# HIVDC_v1p1.net
KiCad netlist of a schematic drawn in EAGLE
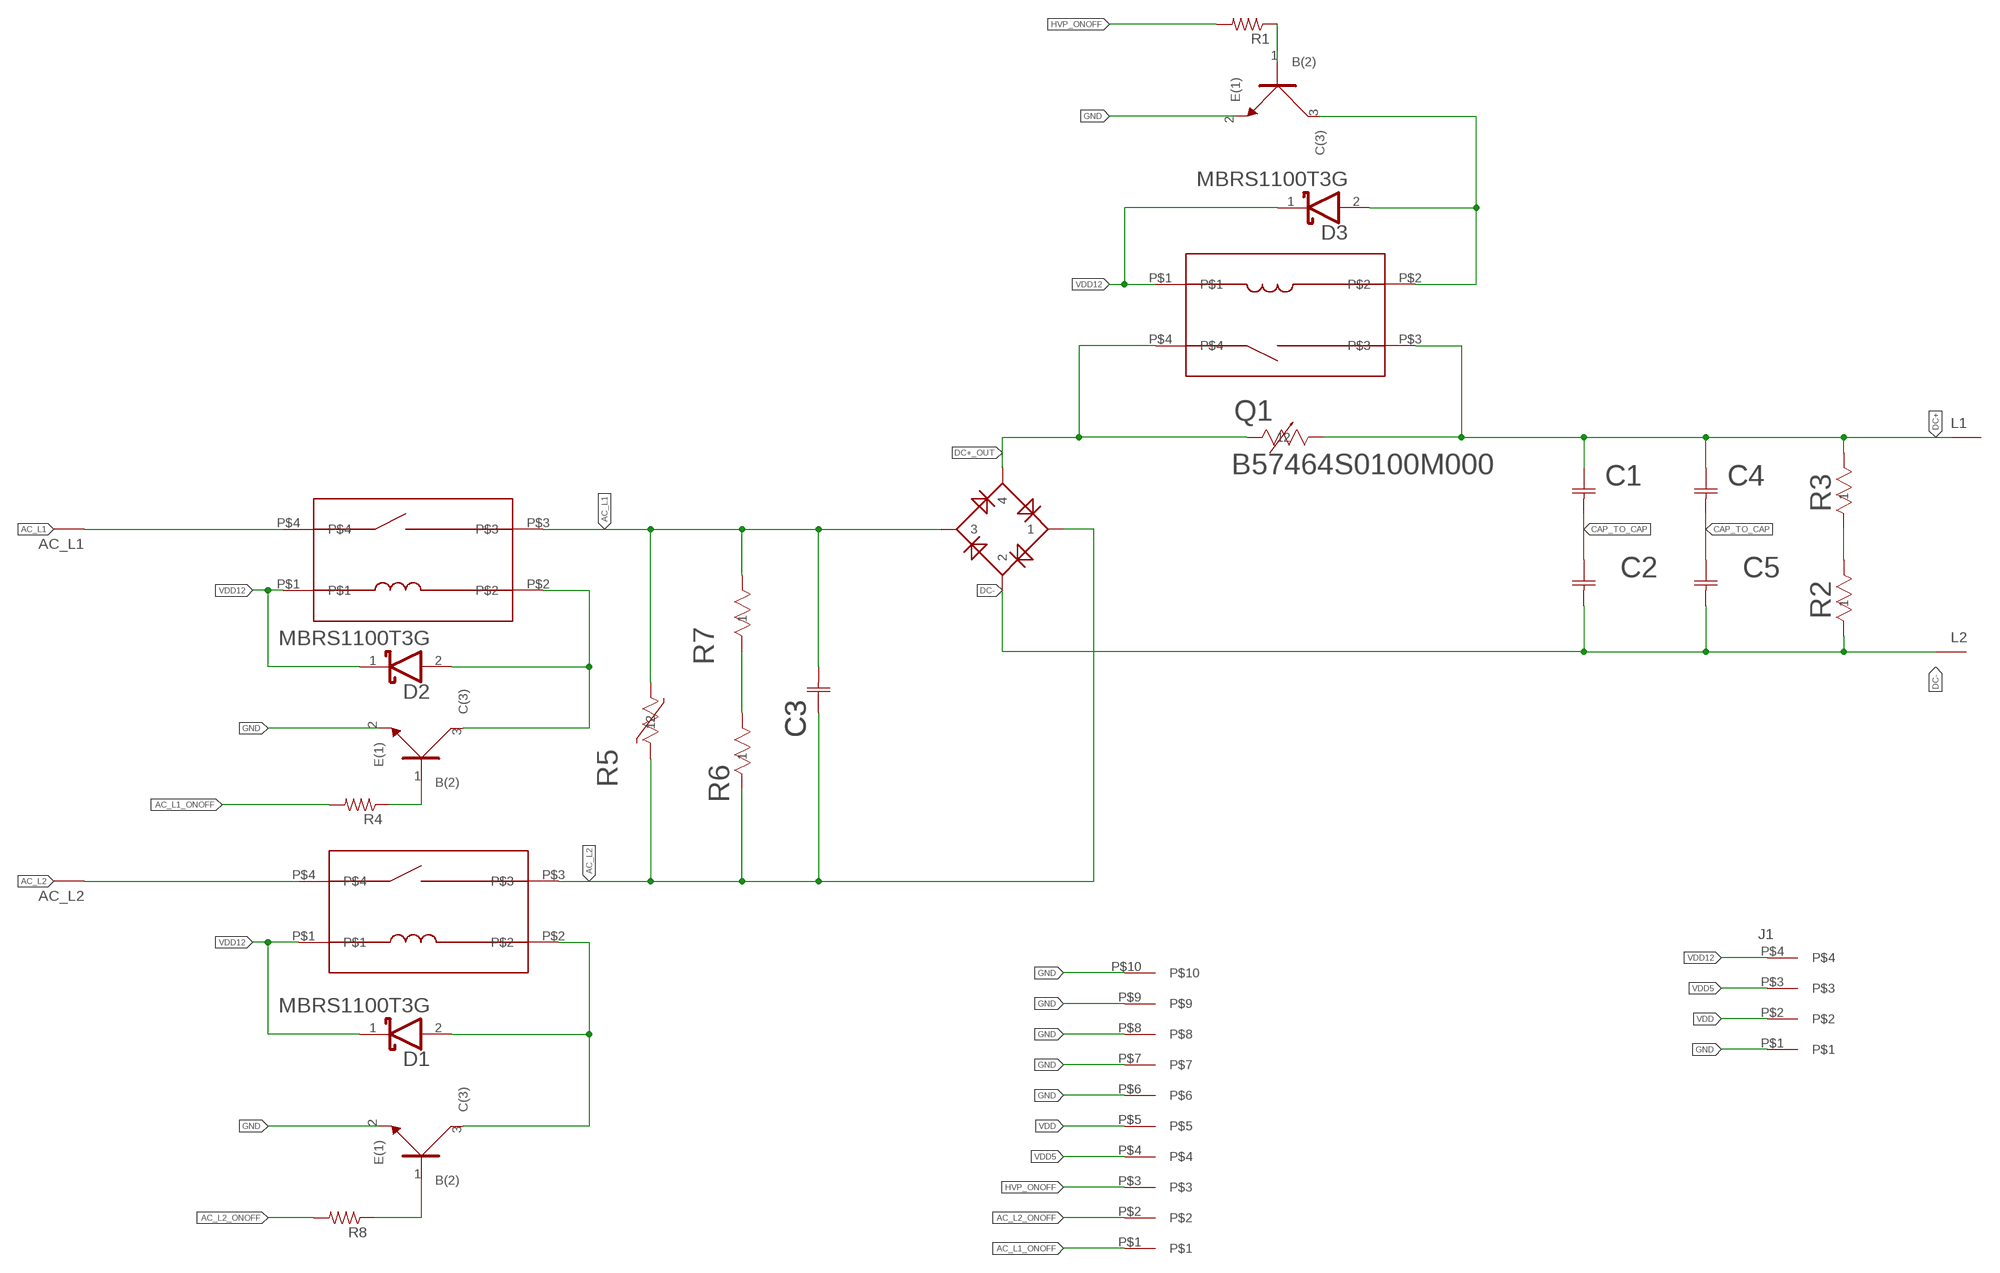
[diagram p0: schematic, sheet 1]

(export (version "E")
  (design (tool "Eeschema 10.0.6"))
  (components
    (comp (ref "AC_L1")
      (value "AC_240V_N_15A")
      (footprint "eagle-import:AC_240V_L1_15A")
      (libsource (lib "eagle-import") (part "AC_240V_N_15A"))
    )
    (comp (ref "AC_L2")
      (value "AC_240V_L_15A")
      (footprint "eagle-import:AC_240V_L1_15A")
      (libsource (lib "eagle-import") (part "AC_240V_L_15A"))
    )
    (comp (ref "C1")
      (value "SLP152M250H9P3")
      (footprint "eagle-import:CAP_SLP152M250H9P3_CND")
      (fields (field (name "COPYRIGHT") "Copyright (C) 2018 Accelerated Designs. All rights reserved"))
      (libsource (lib "eagle-import") (part "SLP152M250H9P3"))
    )
    (comp (ref "C2")
      (value "SLP152M250H9P3")
      (footprint "eagle-import:CAP_SLP152M250H9P3_CND")
      (fields (field (name "COPYRIGHT") "Copyright (C) 2018 Accelerated Designs. All rights reserved"))
      (libsource (lib "eagle-import") (part "SLP152M250H9P3"))
    )
    (comp (ref "C3")
      (value "B32922C3104K")
      (footprint "eagle-import:CAP_5.0_X_10.5_X_18.0_EPC")
      (libsource (lib "eagle-import") (part "B32922C3104K"))
    )
    (comp (ref "C4")
      (value "SLP152M250H9P3")
      (footprint "eagle-import:CAP_SLP152M250H9P3_CND")
      (fields (field (name "COPYRIGHT") "Copyright (C) 2018 Accelerated Designs. All rights reserved"))
      (libsource (lib "eagle-import") (part "SLP152M250H9P3"))
    )
    (comp (ref "C5")
      (value "SLP152M250H9P3")
      (footprint "eagle-import:CAP_SLP152M250H9P3_CND")
      (fields (field (name "COPYRIGHT") "Copyright (C) 2018 Accelerated Designs. All rights reserved"))
      (libsource (lib "eagle-import") (part "SLP152M250H9P3"))
    )
    (comp (ref "D1")
      (value "MBRS1100T3GON_SEMI_MBRS1100T3G_0_0")
      (footprint "eagle-import:SMB")
      (fields
        (field (name "3DS_PART_NUMBER") "417-00000")
        (field (name "DIGIKEY_PART_NUMBER") "MBRS1100T3GOSCT-ND")
        (field (name "MF") "ON Semi")
      )
      (libsource (lib "eagle-import") (part "MBRS1100T3GON_SEMI_MBRS1100T3G_0_0"))
    )
    (comp (ref "D2")
      (value "MBRS1100T3GON_SEMI_MBRS1100T3G_0_0")
      (footprint "eagle-import:SMB")
      (fields
        (field (name "3DS_PART_NUMBER") "417-00000")
        (field (name "DIGIKEY_PART_NUMBER") "MBRS1100T3GOSCT-ND")
        (field (name "MF") "ON Semi")
      )
      (libsource (lib "eagle-import") (part "MBRS1100T3GON_SEMI_MBRS1100T3G_0_0"))
    )
    (comp (ref "D3")
      (value "MBRS1100T3GON_SEMI_MBRS1100T3G_0_0")
      (footprint "eagle-import:SMB")
      (fields
        (field (name "3DS_PART_NUMBER") "417-00000")
        (field (name "DIGIKEY_PART_NUMBER") "MBRS1100T3GOSCT-ND")
        (field (name "MF") "ON Semi")
      )
      (libsource (lib "eagle-import") (part "MBRS1100T3GON_SEMI_MBRS1100T3G_0_0"))
    )
    (comp (ref "J1")
      (value "4-pos")
      (footprint "eagle-import:1X4_3.81MM_PITCH")
      (fields (field (name "PARTNO") "691322310004"))
      (libsource (lib "eagle-import") (part "3.81MM_1_X_4_RT_ANGLE_PLUG_HEADER"))
    )
    (comp (ref "L1")
      (value "DC_HI_V")
      (footprint "eagle-import:AC_240V_L1_15A")
      (libsource (lib "eagle-import") (part "DC_HI_V"))
    )
    (comp (ref "L2")
      (value "DC_HI_V")
      (footprint "eagle-import:AC_240V_L1_15A")
      (libsource (lib "eagle-import") (part "DC_HI_V"))
    )
    (comp (ref "Q1")
      (value "B57464S0100M000")
      (footprint "eagle-import:TRES_B57464S0XXXM000_EPC")
      (fields (field (name "COPYRIGHT") "Copyright (C) 2018 Accelerated Designs. All rights reserved"))
      (libsource (lib "eagle-import") (part "B57464S0100M000"))
    )
    (comp (ref "R1")
      (value "R_0402")
      (footprint "eagle-import:0402")
      (libsource (lib "eagle-import") (part "R_0402"))
    )
    (comp (ref "R2")
      (value "CRCW1206220KJNEAHPRES_V1206_VIS-M")
      (footprint "eagle-import:RES_V1206_VIS-M")
      (fields (field (name "MANUFACTURER_PART_NUMBER") "CRCW1206220KJNEAHP"))
      (libsource (lib "eagle-import") (part "CRCW1206220KJNEAHPRES_V1206_VIS-M"))
    )
    (comp (ref "R3")
      (value "CRCW1206220KJNEAHPRES_V1206_VIS-M")
      (footprint "eagle-import:RES_V1206_VIS-M")
      (fields (field (name "MANUFACTURER_PART_NUMBER") "CRCW1206220KJNEAHP"))
      (libsource (lib "eagle-import") (part "CRCW1206220KJNEAHPRES_V1206_VIS-M"))
    )
    (comp (ref "R4")
      (value "R_0402")
      (footprint "eagle-import:0402")
      (libsource (lib "eagle-import") (part "R_0402"))
    )
    (comp (ref "R5")
      (value "VDRUS10T510BSE")
      (footprint "eagle-import:VRES_VDRUS10T460BSE_VIS")
      (fields (field (name "COPYRIGHT") "Copyright (C) 2018 Accelerated Designs. All rights reserved"))
      (libsource (lib "eagle-import") (part "VDRUS10T510BSE"))
    )
    (comp (ref "R6")
      (value "CRCW1206220KJNEAHPRES_V1206_VIS-M")
      (footprint "eagle-import:RES_V1206_VIS-M")
      (fields (field (name "MANUFACTURER_PART_NUMBER") "CRCW1206220KJNEAHP"))
      (libsource (lib "eagle-import") (part "CRCW1206220KJNEAHPRES_V1206_VIS-M"))
    )
    (comp (ref "R7")
      (value "CRCW1206220KJNEAHPRES_V1206_VIS-M")
      (footprint "eagle-import:RES_V1206_VIS-M")
      (fields (field (name "MANUFACTURER_PART_NUMBER") "CRCW1206220KJNEAHP"))
      (libsource (lib "eagle-import") (part "CRCW1206220KJNEAHPRES_V1206_VIS-M"))
    )
    (comp (ref "R8")
      (value "R_0402")
      (footprint "eagle-import:0402")
      (libsource (lib "eagle-import") (part "R_0402"))
    )
    (comp (ref "RL1")
      (value "J120D1AS12VDCP")
      (footprint "eagle-import:J120D")
      (libsource (lib "eagle-import") (part "J120D1AS12VDCP"))
    )
    (comp (ref "RL2")
      (value "J120D1AS12VDCP")
      (footprint "eagle-import:J120D")
      (libsource (lib "eagle-import") (part "J120D1AS12VDCP"))
    )
    (comp (ref "RL3")
      (value "J120D1AS12VDCP")
      (footprint "eagle-import:J120D")
      (libsource (lib "eagle-import") (part "J120D1AS12VDCP"))
    )
    (comp (ref "U$1")
      (value "KBPC5010W-G")
      (footprint "eagle-import:KBPC-W_THRU")
      (libsource (lib "eagle-import") (part "KBPC5010W-G"))
    )
    (comp (ref "U$3")
      (value "1_X_10_HEADER_GENERIC_.1INCH")
      (footprint "eagle-import:HEADER_1_X_10_.1_INCH")
      (libsource (lib "eagle-import") (part "1_X_10_HEADER_GENERIC_.1INCH"))
    )
    (comp (ref "U1")
      (value "NPN")
      (footprint "eagle-import:SOT323")
      (fields (field (name "PARTNO") "BC846BW_NPN"))
      (libsource (lib "eagle-import") (part "BC846BW"))
    )
    (comp (ref "U2")
      (value "NPN")
      (footprint "eagle-import:SOT323")
      (fields (field (name "PARTNO") "BC846BW_NPN"))
      (libsource (lib "eagle-import") (part "BC846BW"))
    )
    (comp (ref "U3")
      (value "NPN")
      (footprint "eagle-import:SOT323")
      (fields (field (name "PARTNO") "BC846BW_NPN"))
      (libsource (lib "eagle-import") (part "BC846BW"))
    )
  )
  (nets
    (net (code "1") (name "AC_L1") (class "Default")
      (node (ref "AC_L1") (pin "P$1") (pinfunction "P$1_P$1") (pintype "passive"))
      (node (ref "C3") (pin "2") (pinfunction "2_2") (pintype "passive"))
      (node (ref "R5") (pin "1") (pinfunction "11_1") (pintype "passive"))
      (node (ref "R7") (pin "2") (pinfunction "2_2") (pintype "passive"))
      (node (ref "RL2") (pin "P$3") (pinfunction "P$3_P$3") (pintype "bidirectional"))
      (node (ref "RL2") (pin "P$4") (pinfunction "P$4_P$4") (pintype "bidirectional"))
      (node (ref "U$1") (pin "3") (pinfunction "3_3") (pintype "passive"))
    )
    (net (code "2") (name "AC_L1_ONOFF") (class "Default")
      (node (ref "R4") (pin "P$2") (pinfunction "2_P$2") (pintype "passive"))
      (node (ref "U$3") (pin "P$1") (pinfunction "P$1_P$1") (pintype "bidirectional"))
    )
    (net (code "3") (name "AC_L2") (class "Default")
      (node (ref "AC_L2") (pin "P$1") (pinfunction "P$1_P$1") (pintype "passive"))
      (node (ref "C3") (pin "1") (pinfunction "1_1") (pintype "passive"))
      (node (ref "R5") (pin "2") (pinfunction "12_2") (pintype "passive"))
      (node (ref "R6") (pin "1") (pinfunction "1_1") (pintype "passive"))
      (node (ref "RL3") (pin "P$3") (pinfunction "P$3_P$3") (pintype "bidirectional"))
      (node (ref "RL3") (pin "P$4") (pinfunction "P$4_P$4") (pintype "bidirectional"))
      (node (ref "U$1") (pin "1") (pinfunction "1_1") (pintype "passive"))
    )
    (net (code "4") (name "AC_L2_ONOFF") (class "Default")
      (node (ref "R8") (pin "P$2") (pinfunction "2_P$2") (pintype "passive"))
      (node (ref "U$3") (pin "P$2") (pinfunction "P$2_P$2") (pintype "bidirectional"))
    )
    (net (code "5") (name "CAP_TO_CAP") (class "Default")
      (node (ref "C1") (pin "2") (pinfunction "2_2") (pintype "passive"))
      (node (ref "C2") (pin "1") (pinfunction "1_1") (pintype "passive"))
      (node (ref "C4") (pin "2") (pinfunction "2_2") (pintype "passive"))
      (node (ref "C5") (pin "1") (pinfunction "1_1") (pintype "passive"))
    )
    (net (code "6") (name "DC+") (class "Default")
      (node (ref "C1") (pin "1") (pinfunction "1_1") (pintype "passive"))
      (node (ref "C4") (pin "1") (pinfunction "1_1") (pintype "passive"))
      (node (ref "L1") (pin "P$1") (pinfunction "P$1_P$1") (pintype "passive"))
      (node (ref "Q1") (pin "1") (pinfunction "11_1") (pintype "passive"))
      (node (ref "R3") (pin "2") (pinfunction "2_2") (pintype "passive"))
      (node (ref "RL1") (pin "P$3") (pinfunction "P$3_P$3") (pintype "bidirectional"))
    )
    (net (code "7") (name "DC+_OUT") (class "Default")
      (node (ref "Q1") (pin "2") (pinfunction "12_2") (pintype "passive"))
      (node (ref "RL1") (pin "P$4") (pinfunction "P$4_P$4") (pintype "bidirectional"))
      (node (ref "U$1") (pin "4") (pinfunction "4_4") (pintype "passive"))
    )
    (net (code "8") (name "DC-") (class "Default")
      (node (ref "C2") (pin "2") (pinfunction "2_2") (pintype "passive"))
      (node (ref "C5") (pin "2") (pinfunction "2_2") (pintype "passive"))
      (node (ref "L2") (pin "P$1") (pinfunction "P$1_P$1") (pintype "passive"))
      (node (ref "R2") (pin "1") (pinfunction "1_1") (pintype "passive"))
      (node (ref "U$1") (pin "2") (pinfunction "2_2") (pintype "passive"))
    )
    (net (code "9") (name "GND") (class "Default")
      (node (ref "J1") (pin "P$1") (pinfunction "P$1_P$1") (pintype "bidirectional"))
      (node (ref "U$3") (pin "P$10") (pinfunction "P$10_P$10") (pintype "bidirectional"))
      (node (ref "U$3") (pin "P$6") (pinfunction "P$6_P$6") (pintype "bidirectional"))
      (node (ref "U$3") (pin "P$7") (pinfunction "P$7_P$7") (pintype "bidirectional"))
      (node (ref "U$3") (pin "P$8") (pinfunction "P$8_P$8") (pintype "bidirectional"))
      (node (ref "U$3") (pin "P$9") (pinfunction "P$9_P$9") (pintype "bidirectional"))
      (node (ref "U1") (pin "2") (pinfunction "E(1)_2") (pintype "output"))
      (node (ref "U2") (pin "2") (pinfunction "E(1)_2") (pintype "output"))
      (node (ref "U3") (pin "2") (pinfunction "E(1)_2") (pintype "output"))
    )
    (net (code "10") (name "HVP_ONOFF") (class "Default")
      (node (ref "R1") (pin "P$2") (pinfunction "2_P$2") (pintype "passive"))
      (node (ref "U$3") (pin "P$3") (pinfunction "P$3_P$3") (pintype "bidirectional"))
    )
    (net (code "11") (name "Net-(D1-ANODE)") (class "Default")
      (node (ref "D1") (pin "2") (pinfunction "ANODE_2") (pintype "passive"))
      (node (ref "RL3") (pin "P$2") (pinfunction "P$2_P$2") (pintype "bidirectional"))
      (node (ref "U3") (pin "3") (pinfunction "C(3)_3") (pintype "input"))
    )
    (net (code "12") (name "Net-(D2-ANODE)") (class "Default")
      (node (ref "D2") (pin "2") (pinfunction "ANODE_2") (pintype "passive"))
      (node (ref "RL2") (pin "P$2") (pinfunction "P$2_P$2") (pintype "bidirectional"))
      (node (ref "U2") (pin "3") (pinfunction "C(3)_3") (pintype "input"))
    )
    (net (code "13") (name "Net-(D3-ANODE)") (class "Default")
      (node (ref "D3") (pin "2") (pinfunction "ANODE_2") (pintype "passive"))
      (node (ref "RL1") (pin "P$2") (pinfunction "P$2_P$2") (pintype "bidirectional"))
      (node (ref "U1") (pin "3") (pinfunction "C(3)_3") (pintype "input"))
    )
    (net (code "14") (name "Net-(R1-1)") (class "Default")
      (node (ref "R1") (pin "P$1") (pinfunction "1_P$1") (pintype "passive"))
      (node (ref "U1") (pin "1") (pinfunction "B(2)_1") (pintype "input"))
    )
    (net (code "15") (name "Net-(R2-Pad2)") (class "Default")
      (node (ref "R2") (pin "2") (pinfunction "2_2") (pintype "passive"))
      (node (ref "R3") (pin "1") (pinfunction "1_1") (pintype "passive"))
    )
    (net (code "16") (name "Net-(R4-1)") (class "Default")
      (node (ref "R4") (pin "P$1") (pinfunction "1_P$1") (pintype "passive"))
      (node (ref "U2") (pin "1") (pinfunction "B(2)_1") (pintype "input"))
    )
    (net (code "17") (name "Net-(R6-Pad2)") (class "Default")
      (node (ref "R6") (pin "2") (pinfunction "2_2") (pintype "passive"))
      (node (ref "R7") (pin "1") (pinfunction "1_1") (pintype "passive"))
    )
    (net (code "18") (name "Net-(R8-1)") (class "Default")
      (node (ref "R8") (pin "P$1") (pinfunction "1_P$1") (pintype "passive"))
      (node (ref "U3") (pin "1") (pinfunction "B(2)_1") (pintype "input"))
    )
    (net (code "19") (name "VDD") (class "Default")
      (node (ref "J1") (pin "P$2") (pinfunction "P$2_P$2") (pintype "bidirectional"))
      (node (ref "U$3") (pin "P$5") (pinfunction "P$5_P$5") (pintype "bidirectional"))
    )
    (net (code "20") (name "VDD5") (class "Default")
      (node (ref "J1") (pin "P$3") (pinfunction "P$3_P$3") (pintype "bidirectional"))
      (node (ref "U$3") (pin "P$4") (pinfunction "P$4_P$4") (pintype "bidirectional"))
    )
    (net (code "21") (name "VDD12") (class "Default")
      (node (ref "D1") (pin "1") (pinfunction "CATHODE_1") (pintype "passive"))
      (node (ref "D2") (pin "1") (pinfunction "CATHODE_1") (pintype "passive"))
      (node (ref "D3") (pin "1") (pinfunction "CATHODE_1") (pintype "passive"))
      (node (ref "J1") (pin "P$4") (pinfunction "P$4_P$4") (pintype "bidirectional"))
      (node (ref "RL1") (pin "P$1") (pinfunction "P$1_P$1") (pintype "bidirectional"))
      (node (ref "RL2") (pin "P$1") (pinfunction "P$1_P$1") (pintype "bidirectional"))
      (node (ref "RL3") (pin "P$1") (pinfunction "P$1_P$1") (pintype "bidirectional"))
    )
  )
)
